# switch.net
KiCad netlist of a schematic drawn in EAGLE
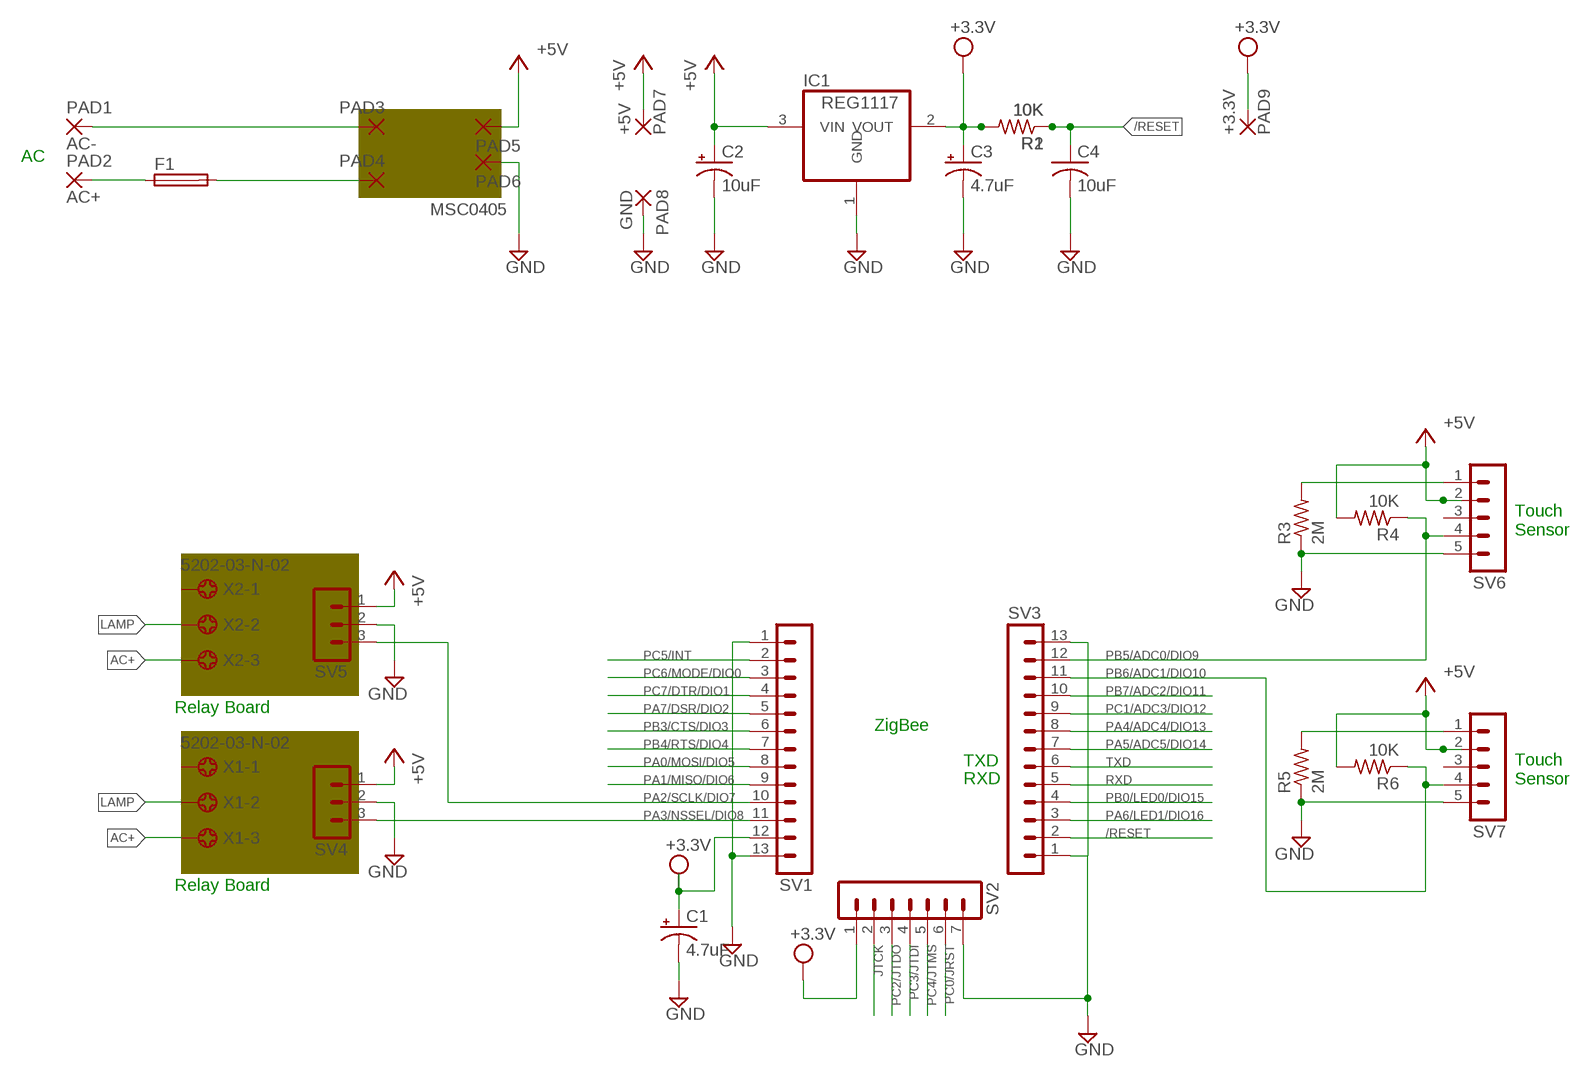
[diagram p0: schematic, sheet 1]

(export (version "E")
  (design (tool "Eeschema 10.0.6"))
  (components
    (comp (ref "C1")
      (value "4.7uF")
      (footprint "eagle-import:SANYO-OSCON_SMD_A5")
      (libsource (lib "eagle-import") (part "CPOL-USSANYO_SMD_A5"))
    )
    (comp (ref "C2")
      (value "10uF")
      (footprint "eagle-import:SANYO-OSCON_SMD_A5")
      (libsource (lib "eagle-import") (part "CPOL-USSANYO_SMD_A5"))
    )
    (comp (ref "C3")
      (value "4.7uF")
      (footprint "eagle-import:SANYO-OSCON_SMD_A5")
      (libsource (lib "eagle-import") (part "CPOL-USSANYO_SMD_A5"))
    )
    (comp (ref "C4")
      (value "10uF")
      (footprint "eagle-import:C1206")
      (libsource (lib "eagle-import") (part "C-USC1206"))
    )
    (comp (ref "F1")
      (value "GSH15")
      (footprint "eagle-import:GSH15")
      (fields (field (name "MPN") "64900001039"))
      (libsource (lib "eagle-import") (part "GSH15"))
    )
    (comp (ref "IC1")
      (value "REG1117")
      (footprint "eagle-import:SOT223")
      (libsource (lib "eagle-import") (part "REG1117"))
    )
    (comp (ref "PAD1")
      (value "AC-")
      (footprint "eagle-import:2,54_1,0")
      (libsource (lib "eagle-import") (part "2,54/1,0"))
    )
    (comp (ref "PAD2")
      (value "AC+")
      (footprint "eagle-import:2,54_1,0")
      (libsource (lib "eagle-import") (part "2,54/1,0"))
    )
    (comp (ref "PAD3")
      (value "2,54/0,8")
      (footprint "eagle-import:2,54_0,8")
      (libsource (lib "eagle-import") (part "2,54/0,8"))
    )
    (comp (ref "PAD4")
      (value "2,54/0,8")
      (footprint "eagle-import:2,54_0,8")
      (libsource (lib "eagle-import") (part "2,54/0,8"))
    )
    (comp (ref "PAD5")
      (value "2,54/0,8")
      (footprint "eagle-import:2,54_0,8")
      (libsource (lib "eagle-import") (part "2,54/0,8"))
    )
    (comp (ref "PAD6")
      (value "2,54/0,8")
      (footprint "eagle-import:2,54_0,8")
      (libsource (lib "eagle-import") (part "2,54/0,8"))
    )
    (comp (ref "PAD7")
      (value "+5V")
      (footprint "eagle-import:2,54_0,8")
      (libsource (lib "eagle-import") (part "2,54/0,8"))
    )
    (comp (ref "PAD8")
      (value "GND")
      (footprint "eagle-import:2,54_0,8")
      (libsource (lib "eagle-import") (part "2,54/0,8"))
    )
    (comp (ref "PAD9")
      (value "+3.3V")
      (footprint "eagle-import:2,54_0,8")
      (libsource (lib "eagle-import") (part "2,54/0,8"))
    )
    (comp (ref "R1")
      (value "10K")
      (footprint "eagle-import:M1206")
      (libsource (lib "eagle-import") (part "R-US_M1206"))
    )
    (comp (ref "R2")
      (value "10K")
      (footprint "eagle-import:M1206")
      (libsource (lib "eagle-import") (part "R-US_M1206"))
    )
    (comp (ref "R3")
      (value "2M")
      (footprint "eagle-import:M1206")
      (libsource (lib "eagle-import") (part "R-US_M1206"))
    )
    (comp (ref "R4")
      (value "10K")
      (footprint "eagle-import:M1206")
      (libsource (lib "eagle-import") (part "R-US_M1206"))
    )
    (comp (ref "R5")
      (value "2M")
      (footprint "eagle-import:M1206")
      (libsource (lib "eagle-import") (part "R-US_M1206"))
    )
    (comp (ref "R6")
      (value "10K")
      (footprint "eagle-import:M1206")
      (libsource (lib "eagle-import") (part "R-US_M1206"))
    )
    (comp (ref "SV1")
      (value "MA13-1")
      (footprint "eagle-import:MA13-1")
      (libsource (lib "eagle-import") (part "MA13-1"))
    )
    (comp (ref "SV2")
      (value "MA07-1")
      (footprint "eagle-import:MA07-1")
      (libsource (lib "eagle-import") (part "MA07-1"))
    )
    (comp (ref "SV3")
      (value "MA13-1")
      (footprint "eagle-import:MA13-1")
      (libsource (lib "eagle-import") (part "MA13-1"))
    )
    (comp (ref "SV4")
      (value "MA03-1")
      (footprint "eagle-import:MA03-1")
      (libsource (lib "eagle-import") (part "MA03-1"))
    )
    (comp (ref "SV5")
      (value "MA03-1")
      (footprint "eagle-import:MA03-1")
      (libsource (lib "eagle-import") (part "MA03-1"))
    )
    (comp (ref "SV6")
      (value "MA05-1")
      (footprint "eagle-import:MA05-1")
      (libsource (lib "eagle-import") (part "MA05-1"))
    )
    (comp (ref "SV7")
      (value "MA05-1")
      (footprint "eagle-import:MA05-1")
      (libsource (lib "eagle-import") (part "MA05-1"))
    )
    (comp (ref "X1")
      (value "5202-03-N-02")
      (footprint "eagle-import:5202-03-N-02")
      (libsource (lib "eagle-import") (part "5202-03-N-02"))
    )
    (comp (ref "X2")
      (value "5202-03-N-02")
      (footprint "eagle-import:5202-03-N-02")
      (libsource (lib "eagle-import") (part "5202-03-N-02"))
    )
  )
  (nets
    (net (code "1") (name "+3.3V") (class "Default")
      (node (ref "C1") (pin "+") (pinfunction "+_+") (pintype "passive"))
      (node (ref "C3") (pin "+") (pinfunction "+_+") (pintype "passive"))
      (node (ref "IC1") (pin "2") (pinfunction "VOUT_2") (pintype "output"))
      (node (ref "PAD9") (pin "1") (pinfunction "P_1") (pintype "passive"))
      (node (ref "R1") (pin "2") (pinfunction "2_2") (pintype "passive"))
      (node (ref "R2") (pin "2") (pinfunction "2_2") (pintype "passive"))
      (node (ref "SV1") (pin "12") (pinfunction "12_12") (pintype "passive"))
      (node (ref "SV2") (pin "1") (pinfunction "1_1") (pintype "passive"))
    )
    (net (code "2") (name "+5V") (class "Default")
      (node (ref "C2") (pin "+") (pinfunction "+_+") (pintype "passive"))
      (node (ref "IC1") (pin "3") (pinfunction "VIN_3") (pintype "input"))
      (node (ref "PAD5") (pin "1") (pinfunction "P_1") (pintype "passive"))
      (node (ref "PAD7") (pin "1") (pinfunction "P_1") (pintype "passive"))
      (node (ref "R4") (pin "2") (pinfunction "2_2") (pintype "passive"))
      (node (ref "R6") (pin "2") (pinfunction "2_2") (pintype "passive"))
      (node (ref "SV4") (pin "1") (pinfunction "1_1") (pintype "passive"))
      (node (ref "SV5") (pin "1") (pinfunction "1_1") (pintype "passive"))
      (node (ref "SV6") (pin "2") (pinfunction "2_2") (pintype "passive"))
      (node (ref "SV7") (pin "2") (pinfunction "2_2") (pintype "passive"))
    )
    (net (code "3") (name "/JTCK") (class "Default")
      (node (ref "SV2") (pin "2") (pinfunction "2_2") (pintype "passive"))
    )
    (net (code "4") (name "/PA0{slash}MOSI{slash}DIO5") (class "Default")
      (node (ref "SV1") (pin "8") (pinfunction "8_8") (pintype "passive"))
    )
    (net (code "5") (name "/PA1{slash}MISO{slash}DIO6") (class "Default")
      (node (ref "SV1") (pin "9") (pinfunction "9_9") (pintype "passive"))
    )
    (net (code "6") (name "/PA2{slash}SCLK{slash}DIO7") (class "Default")
      (node (ref "SV1") (pin "10") (pinfunction "10_10") (pintype "passive"))
      (node (ref "SV5") (pin "3") (pinfunction "3_3") (pintype "passive"))
    )
    (net (code "7") (name "/PA3{slash}NSSEL{slash}DIO8") (class "Default")
      (node (ref "SV1") (pin "11") (pinfunction "11_11") (pintype "passive"))
      (node (ref "SV4") (pin "3") (pinfunction "3_3") (pintype "passive"))
    )
    (net (code "8") (name "/PA4{slash}ADC4{slash}DIO13") (class "Default")
      (node (ref "SV3") (pin "8") (pinfunction "8_8") (pintype "passive"))
    )
    (net (code "9") (name "/PA5{slash}ADC5{slash}DIO14") (class "Default")
      (node (ref "SV3") (pin "7") (pinfunction "7_7") (pintype "passive"))
    )
    (net (code "10") (name "/PA6{slash}LED1{slash}DIO16") (class "Default")
      (node (ref "SV3") (pin "3") (pinfunction "3_3") (pintype "passive"))
    )
    (net (code "11") (name "/PA7{slash}DSR{slash}DIO2") (class "Default")
      (node (ref "SV1") (pin "5") (pinfunction "5_5") (pintype "passive"))
    )
    (net (code "12") (name "/PB0{slash}LED0{slash}DIO15") (class "Default")
      (node (ref "SV3") (pin "4") (pinfunction "4_4") (pintype "passive"))
    )
    (net (code "13") (name "/PB3{slash}CTS{slash}DIO3") (class "Default")
      (node (ref "SV1") (pin "6") (pinfunction "6_6") (pintype "passive"))
    )
    (net (code "14") (name "/PB4{slash}RTS{slash}DIO4") (class "Default")
      (node (ref "SV1") (pin "7") (pinfunction "7_7") (pintype "passive"))
    )
    (net (code "15") (name "/PB5{slash}ADC0{slash}DIO9") (class "Default")
      (node (ref "R4") (pin "1") (pinfunction "1_1") (pintype "passive"))
      (node (ref "SV3") (pin "12") (pinfunction "12_12") (pintype "passive"))
      (node (ref "SV6") (pin "4") (pinfunction "4_4") (pintype "passive"))
    )
    (net (code "16") (name "/PB6{slash}ADC1{slash}DIO10") (class "Default")
      (node (ref "R6") (pin "1") (pinfunction "1_1") (pintype "passive"))
      (node (ref "SV3") (pin "11") (pinfunction "11_11") (pintype "passive"))
      (node (ref "SV7") (pin "4") (pinfunction "4_4") (pintype "passive"))
    )
    (net (code "17") (name "/PB7{slash}ADC2{slash}DIO11") (class "Default")
      (node (ref "SV3") (pin "10") (pinfunction "10_10") (pintype "passive"))
    )
    (net (code "18") (name "/PC0{slash}JRST") (class "Default")
      (node (ref "SV2") (pin "6") (pinfunction "6_6") (pintype "passive"))
    )
    (net (code "19") (name "/PC1{slash}ADC3{slash}DIO12") (class "Default")
      (node (ref "SV3") (pin "9") (pinfunction "9_9") (pintype "passive"))
    )
    (net (code "20") (name "/PC2{slash}JTDO") (class "Default")
      (node (ref "SV2") (pin "3") (pinfunction "3_3") (pintype "passive"))
    )
    (net (code "21") (name "/PC3{slash}JTDI") (class "Default")
      (node (ref "SV2") (pin "4") (pinfunction "4_4") (pintype "passive"))
    )
    (net (code "22") (name "/PC4{slash}JTMS") (class "Default")
      (node (ref "SV2") (pin "5") (pinfunction "5_5") (pintype "passive"))
    )
    (net (code "23") (name "/PC5{slash}INT") (class "Default")
      (node (ref "SV1") (pin "2") (pinfunction "2_2") (pintype "passive"))
    )
    (net (code "24") (name "/PC6{slash}MODE{slash}DIO0") (class "Default")
      (node (ref "SV1") (pin "3") (pinfunction "3_3") (pintype "passive"))
    )
    (net (code "25") (name "/PC7{slash}DTR{slash}DIO1") (class "Default")
      (node (ref "SV1") (pin "4") (pinfunction "4_4") (pintype "passive"))
    )
    (net (code "26") (name "/RXD") (class "Default")
      (node (ref "SV3") (pin "5") (pinfunction "5_5") (pintype "passive"))
    )
    (net (code "27") (name "/TXD") (class "Default")
      (node (ref "SV3") (pin "6") (pinfunction "6_6") (pintype "passive"))
    )
    (net (code "28") (name "AC+") (class "Default")
      (node (ref "X1") (pin "3") (pinfunction "1_3") (pintype "passive"))
      (node (ref "X2") (pin "3") (pinfunction "1_3") (pintype "passive"))
    )
    (net (code "29") (name "GND") (class "Default")
      (node (ref "C1") (pin "-") (pinfunction "-_-") (pintype "passive"))
      (node (ref "C2") (pin "-") (pinfunction "-_-") (pintype "passive"))
      (node (ref "C3") (pin "-") (pinfunction "-_-") (pintype "passive"))
      (node (ref "C4") (pin "2") (pinfunction "2_2") (pintype "passive"))
      (node (ref "IC1") (pin "1") (pinfunction "GND_1") (pintype "power_in"))
      (node (ref "PAD6") (pin "1") (pinfunction "P_1") (pintype "passive"))
      (node (ref "PAD8") (pin "1") (pinfunction "P_1") (pintype "passive"))
      (node (ref "R3") (pin "1") (pinfunction "1_1") (pintype "passive"))
      (node (ref "R5") (pin "1") (pinfunction "1_1") (pintype "passive"))
      (node (ref "SV1") (pin "1") (pinfunction "1_1") (pintype "passive"))
      (node (ref "SV1") (pin "13") (pinfunction "13_13") (pintype "passive"))
      (node (ref "SV2") (pin "7") (pinfunction "7_7") (pintype "passive"))
      (node (ref "SV3") (pin "1") (pinfunction "1_1") (pintype "passive"))
      (node (ref "SV3") (pin "13") (pinfunction "13_13") (pintype "passive"))
      (node (ref "SV4") (pin "2") (pinfunction "2_2") (pintype "passive"))
      (node (ref "SV5") (pin "2") (pinfunction "2_2") (pintype "passive"))
      (node (ref "SV6") (pin "5") (pinfunction "5_5") (pintype "passive"))
      (node (ref "SV7") (pin "5") (pinfunction "5_5") (pintype "passive"))
    )
    (net (code "30") (name "LAMP") (class "Default")
      (node (ref "X1") (pin "2") (pinfunction "1_2") (pintype "passive"))
      (node (ref "X2") (pin "2") (pinfunction "1_2") (pintype "passive"))
    )
    (net (code "31") (name "Net-(PAD1-P)") (class "Default")
      (node (ref "PAD1") (pin "1") (pinfunction "P_1") (pintype "passive"))
      (node (ref "PAD3") (pin "1") (pinfunction "P_1") (pintype "passive"))
    )
    (net (code "32") (name "Net-(PAD2-P)") (class "Default")
      (node (ref "F1") (pin "1") (pinfunction "1_1") (pintype "passive"))
      (node (ref "PAD2") (pin "1") (pinfunction "P_1") (pintype "passive"))
    )
    (net (code "33") (name "Net-(PAD4-P)") (class "Default")
      (node (ref "F1") (pin "2") (pinfunction "2_2") (pintype "passive"))
      (node (ref "PAD4") (pin "1") (pinfunction "P_1") (pintype "passive"))
    )
    (net (code "34") (name "Net-(R3-Pad2)") (class "Default")
      (node (ref "R3") (pin "2") (pinfunction "2_2") (pintype "passive"))
      (node (ref "SV6") (pin "1") (pinfunction "1_1") (pintype "passive"))
    )
    (net (code "35") (name "Net-(R5-Pad2)") (class "Default")
      (node (ref "R5") (pin "2") (pinfunction "2_2") (pintype "passive"))
      (node (ref "SV7") (pin "1") (pinfunction "1_1") (pintype "passive"))
    )
    (net (code "36") (name "unconnected-(SV6-Pad3)") (class "Default")
      (node (ref "SV6") (pin "3") (pinfunction "3_3") (pintype "passive"))
    )
    (net (code "37") (name "unconnected-(SV7-Pad3)") (class "Default")
      (node (ref "SV7") (pin "3") (pinfunction "3_3") (pintype "passive"))
    )
    (net (code "38") (name "unconnected-(X1-Pad1)") (class "Default")
      (node (ref "X1") (pin "1") (pinfunction "1_1") (pintype "passive"))
    )
    (net (code "39") (name "unconnected-(X2-Pad1)") (class "Default")
      (node (ref "X2") (pin "1") (pinfunction "1_1") (pintype "passive"))
    )
    (net (code "40") (name "{slash}RESET") (class "Default")
      (node (ref "C4") (pin "1") (pinfunction "1_1") (pintype "passive"))
      (node (ref "R1") (pin "1") (pinfunction "1_1") (pintype "passive"))
      (node (ref "R2") (pin "1") (pinfunction "1_1") (pintype "passive"))
      (node (ref "SV3") (pin "2") (pinfunction "2_2") (pintype "passive"))
    )
  )
)
